# rn_mk2.net
KiCad netlist of a schematic drawn in EAGLE
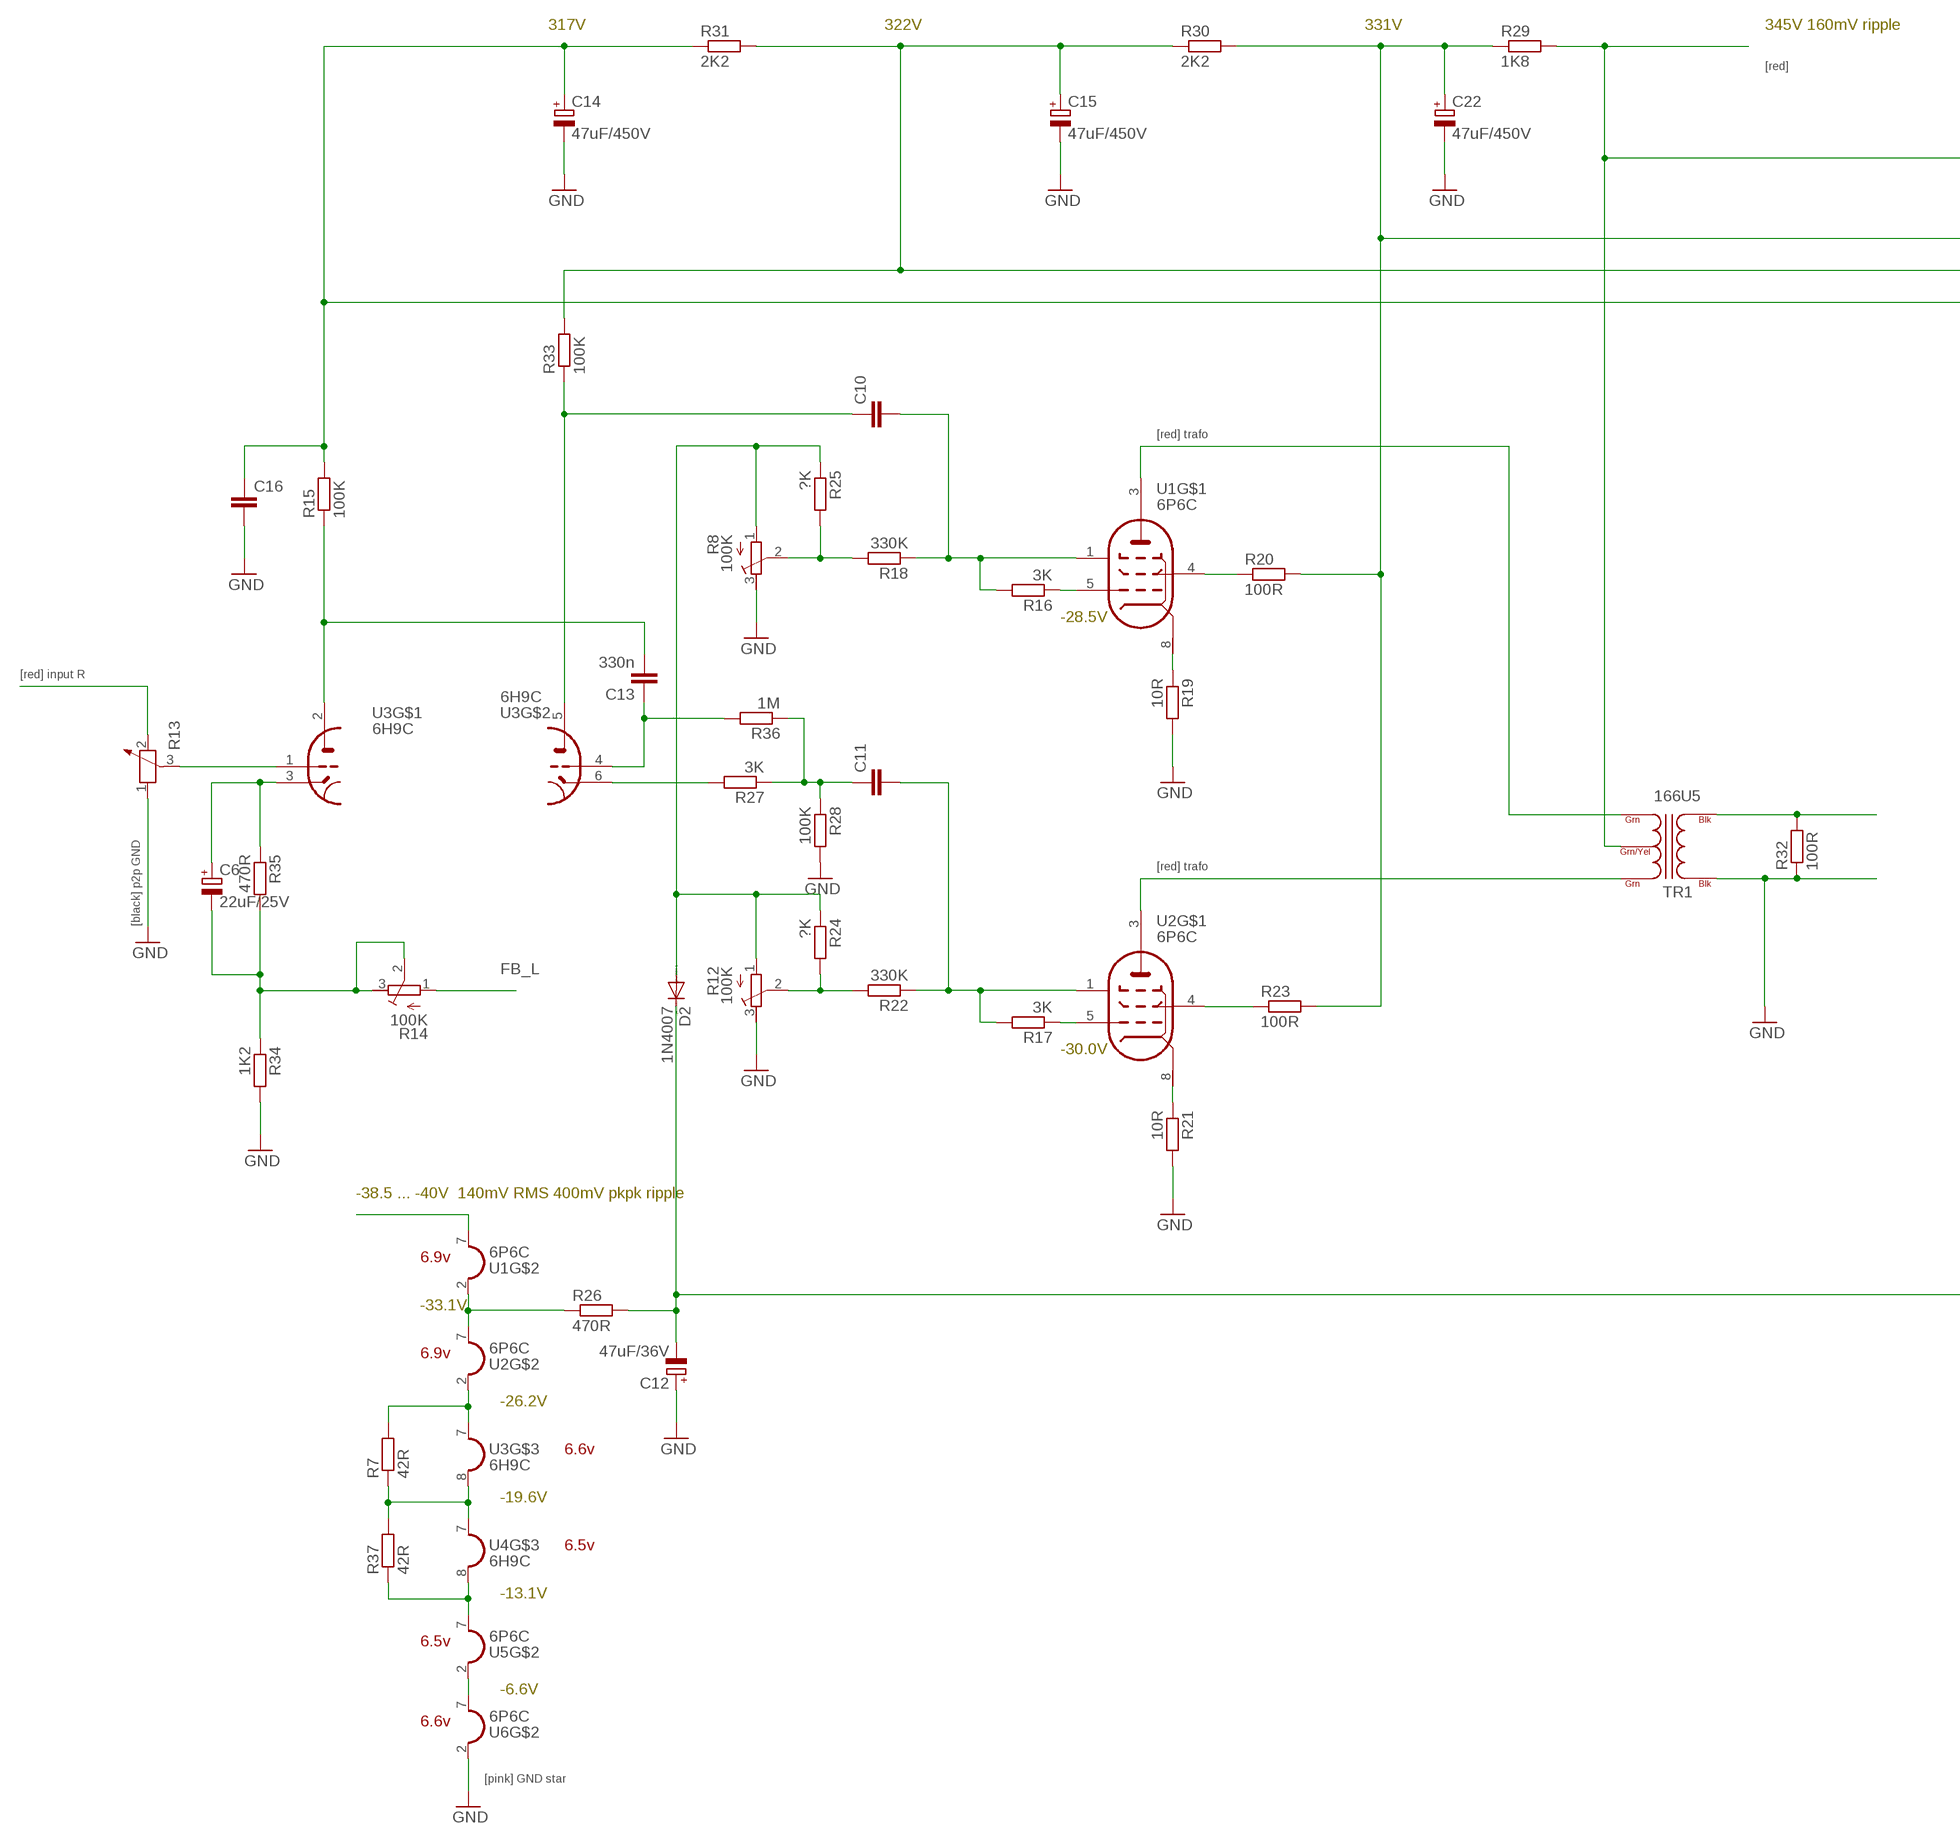
[diagram p0: schematic, sheet 1, part 1 of 2]
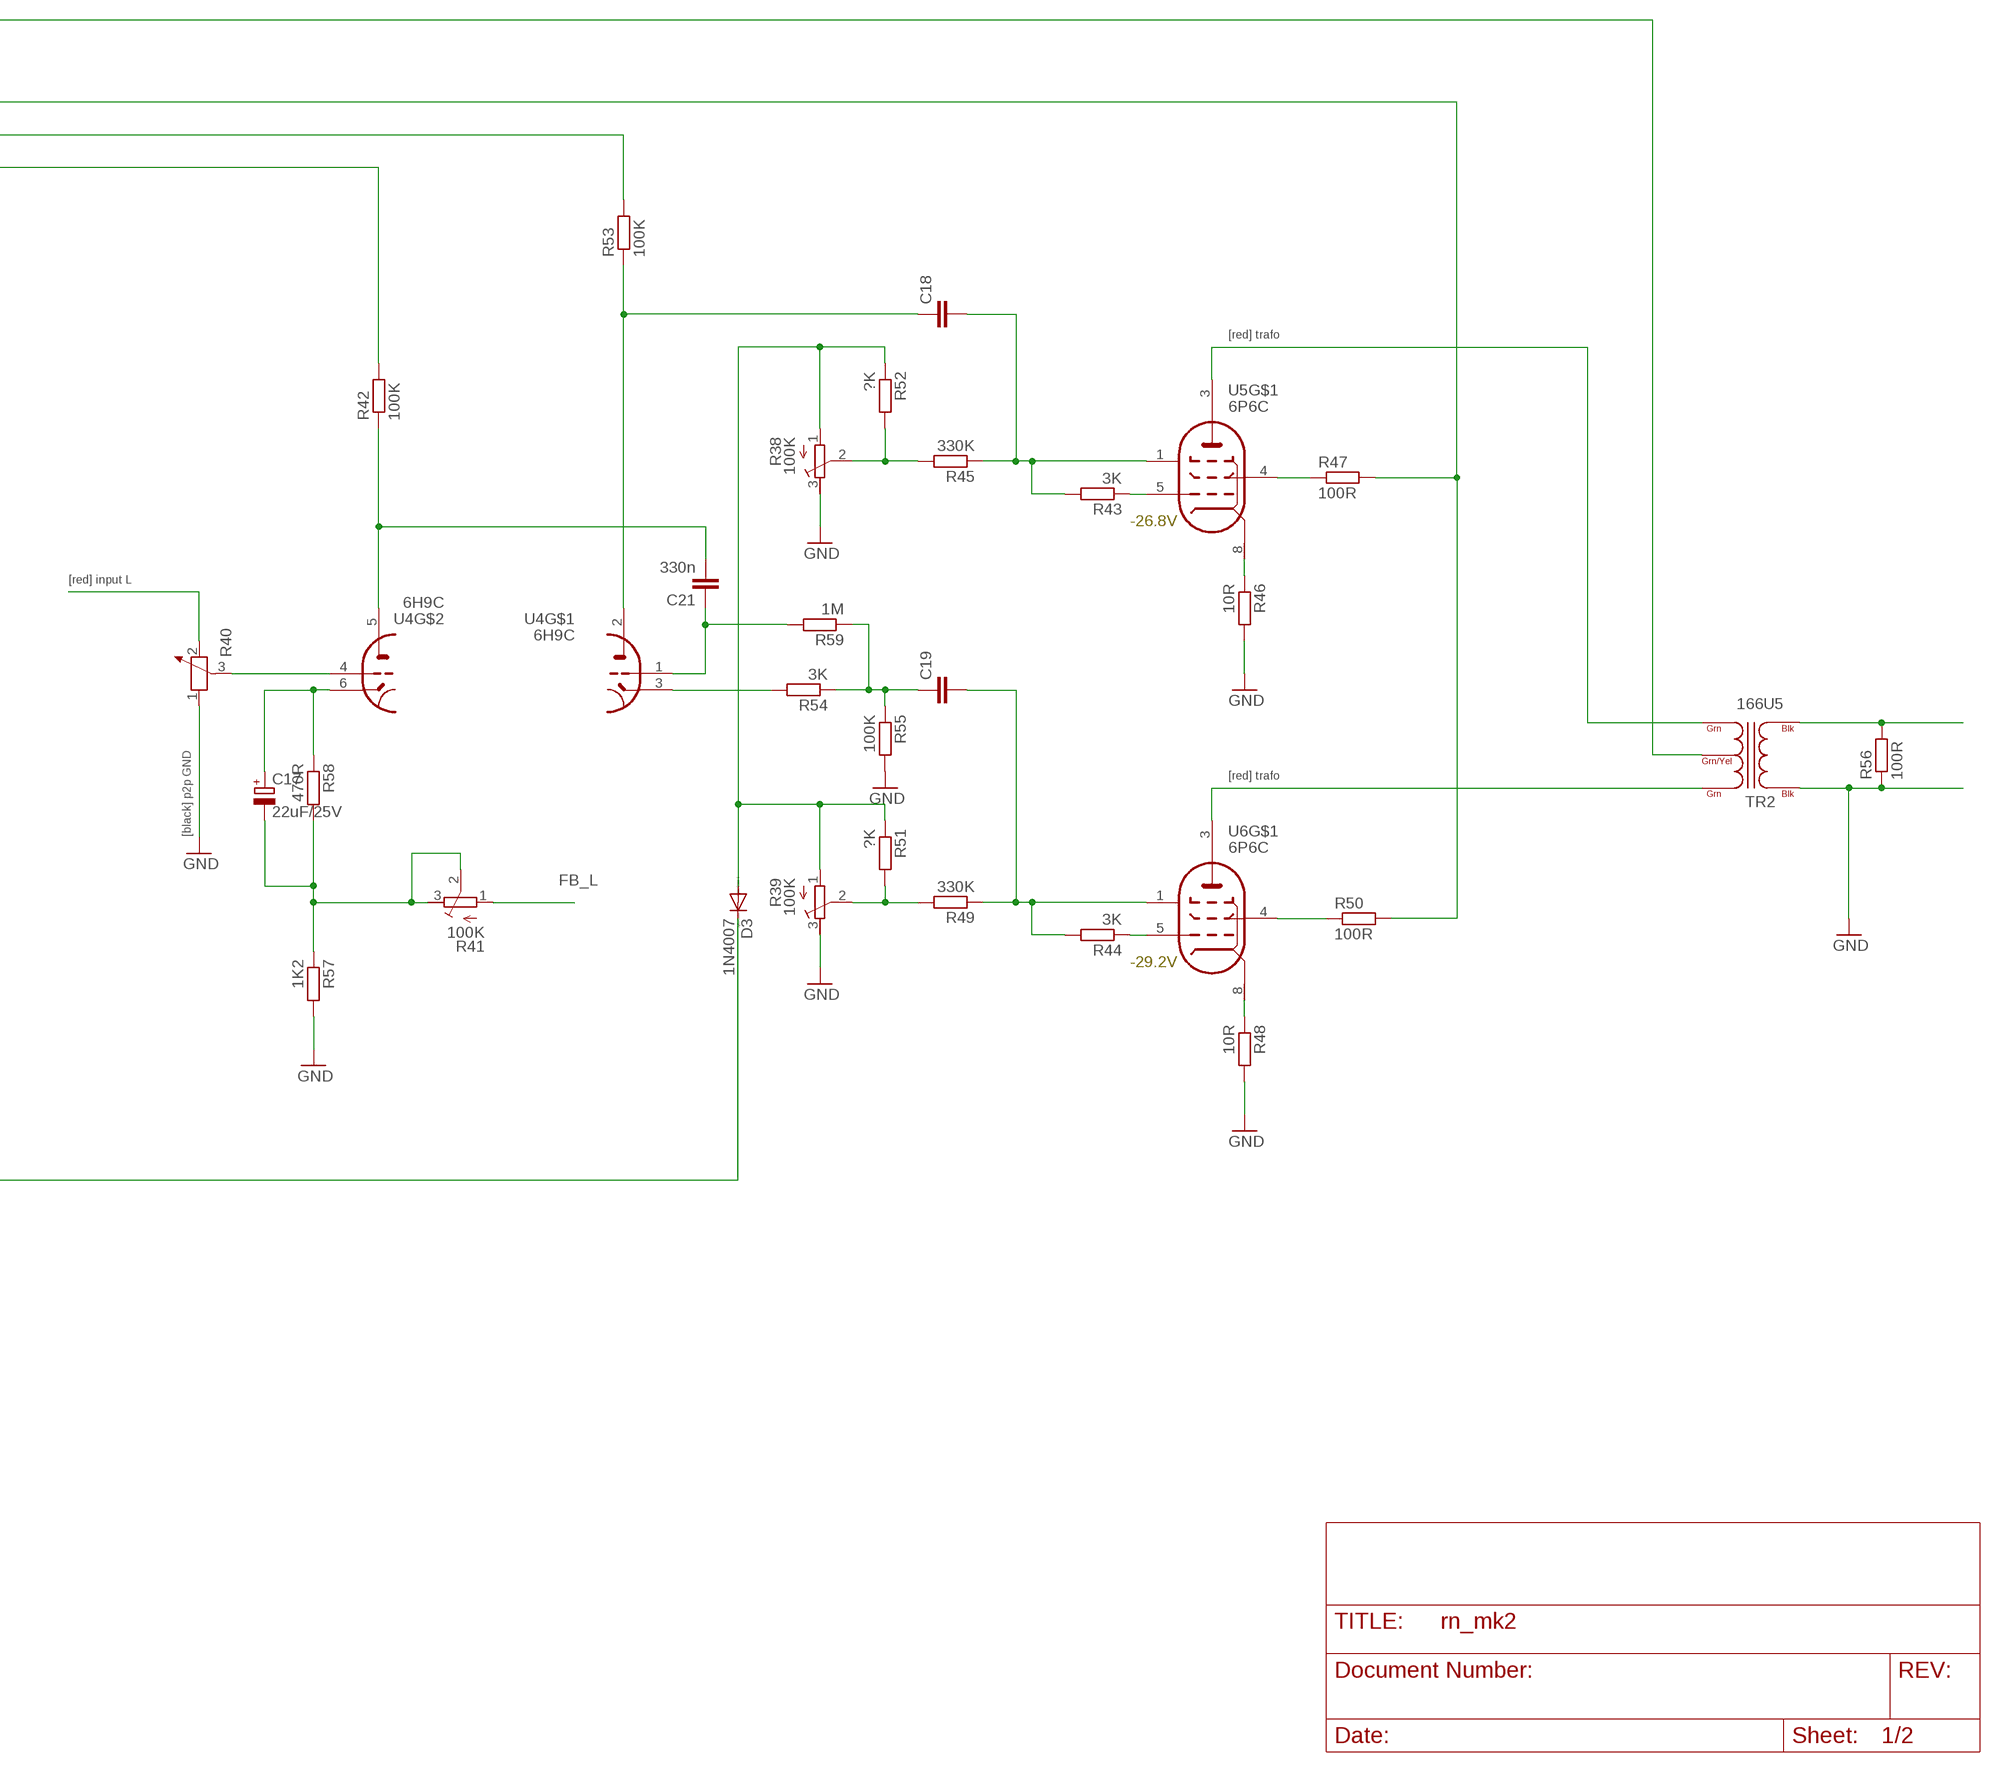
[diagram p1: schematic, sheet 1, part 2 of 2]
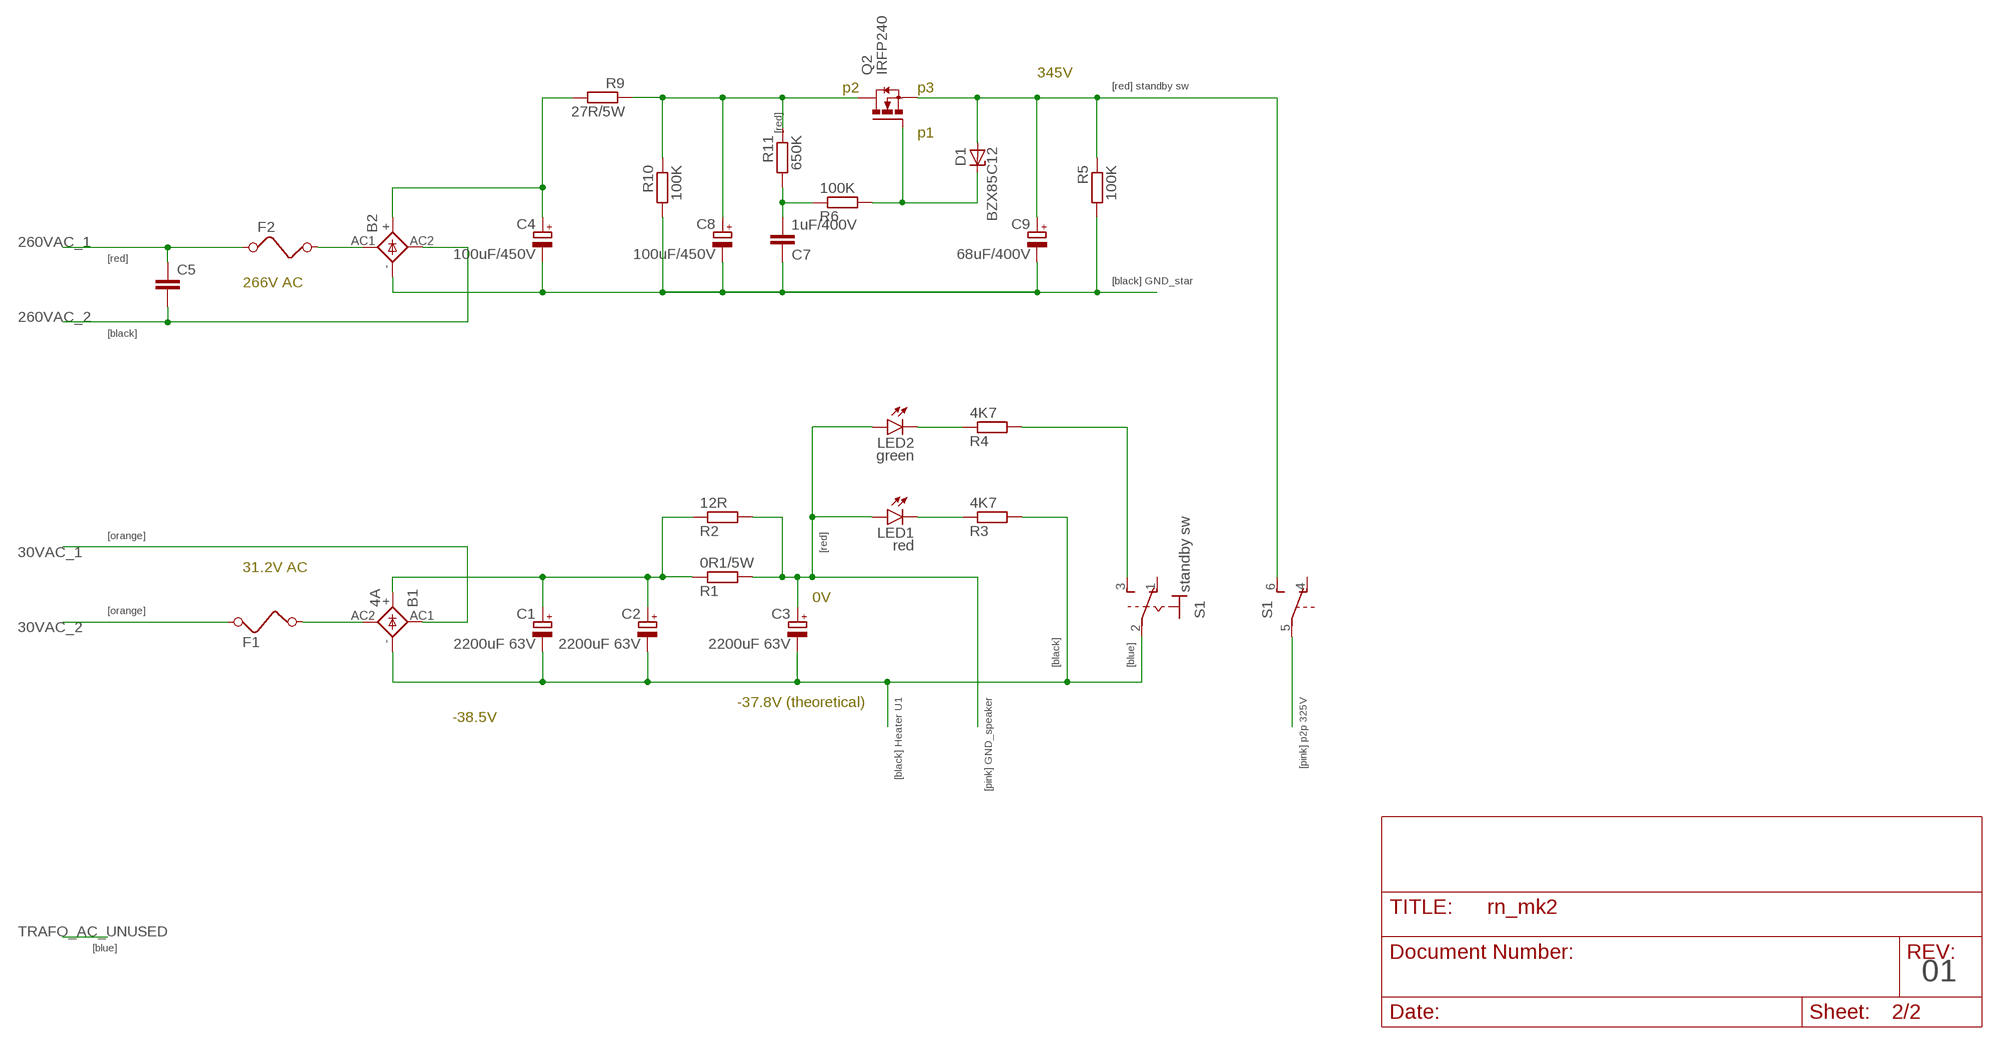
[diagram p2: schematic, sheet 2]

(export (version "E")
  (design (tool "Eeschema 10.0.6"))
  (components
    (comp (ref "B1")
      (value "4A")
      (footprint "eagle-import:DIOTEC_BC5000")
      (libsource (lib "eagle-import") (part "DIOTEC_BC5000"))
    )
    (comp (ref "B2")
      (value "DIOTEC_BC5000")
      (footprint "eagle-import:DIOTEC_BC5000")
      (libsource (lib "eagle-import") (part "DIOTEC_BC5000"))
    )
    (comp (ref "C1")
      (value "2200uF 63V")
      (footprint "eagle-import:E7,5-18")
      (libsource (lib "eagle-import") (part "CPOL-EUE7.5-18"))
    )
    (comp (ref "C2")
      (value "2200uF 63V")
      (footprint "eagle-import:E7,5-18")
      (libsource (lib "eagle-import") (part "CPOL-EUE7.5-18"))
    )
    (comp (ref "C3")
      (value "2200uF 63V")
      (footprint "eagle-import:E7,5-18")
      (libsource (lib "eagle-import") (part "CPOL-EUE7.5-18"))
    )
    (comp (ref "C4")
      (value "100uF/450V")
      (footprint "eagle-import:E7,5-18")
      (libsource (lib "eagle-import") (part "CPOL-EUE7.5-18"))
    )
    (comp (ref "C5")
      (value "C-EU075-032X103")
      (footprint "eagle-import:C075-032X103")
      (libsource (lib "eagle-import") (part "C-EU075-032X103"))
    )
    (comp (ref "C7")
      (value "1uF/400V")
      (footprint "eagle-import:C075-032X103")
      (libsource (lib "eagle-import") (part "C-EU075-032X103"))
    )
    (comp (ref "C8")
      (value "100uF/450V")
      (footprint "eagle-import:E7,5-18")
      (libsource (lib "eagle-import") (part "CPOL-EUE7.5-18"))
    )
    (comp (ref "C9")
      (value "68uF/400V")
      (footprint "eagle-import:E7,5-18")
      (libsource (lib "eagle-import") (part "CPOL-EUE7.5-18"))
    )
    (comp (ref "D1")
      (value "BZX85C12")
      (footprint "eagle-import:DO41Z10")
      (libsource (lib "eagle-import") (part "BZX85"))
    )
    (comp (ref "F1")
      (value "FUSE")
      (footprint "eagle-import:FUSE")
      (libsource (lib "eagle-import") (part "FUSE"))
    )
    (comp (ref "F2")
      (value "FUSE")
      (footprint "eagle-import:FUSE")
      (libsource (lib "eagle-import") (part "FUSE"))
    )
    (comp (ref "LED1")
      (value "red")
      (footprint "eagle-import:LED3MM")
      (libsource (lib "eagle-import") (part "LED3MM"))
    )
    (comp (ref "LED2")
      (value "green")
      (footprint "eagle-import:LED3MM")
      (libsource (lib "eagle-import") (part "LED3MM"))
    )
    (comp (ref "Q2")
      (value "IRFP240")
      (footprint "eagle-import:TO247BV")
      (libsource (lib "eagle-import") (part "IRFP240"))
    )
    (comp (ref "R1")
      (value "0R1/5W")
      (footprint "eagle-import:0922_22")
      (libsource (lib "eagle-import") (part "R-EU_0922/22"))
    )
    (comp (ref "R2")
      (value "12R")
      (footprint "eagle-import:0922_22")
      (libsource (lib "eagle-import") (part "R-EU_0922/22"))
    )
    (comp (ref "R3")
      (value "4K7")
      (footprint "eagle-import:0922_22")
      (libsource (lib "eagle-import") (part "R-EU_0922/22"))
    )
    (comp (ref "R4")
      (value "4K7")
      (footprint "eagle-import:0922_22")
      (libsource (lib "eagle-import") (part "R-EU_0922/22"))
    )
    (comp (ref "R5")
      (value "100K")
      (footprint "eagle-import:0922_22")
      (libsource (lib "eagle-import") (part "R-EU_0922/22"))
    )
    (comp (ref "R6")
      (value "100K")
      (footprint "eagle-import:0922_22")
      (libsource (lib "eagle-import") (part "R-EU_0922/22"))
    )
    (comp (ref "R9")
      (value "27R/5W")
      (footprint "eagle-import:0922_22")
      (libsource (lib "eagle-import") (part "R-EU_0922/22"))
    )
    (comp (ref "R10")
      (value "100K")
      (footprint "eagle-import:0922_22")
      (libsource (lib "eagle-import") (part "R-EU_0922/22"))
    )
    (comp (ref "R11")
      (value "650K")
      (footprint "eagle-import:0922_22")
      (libsource (lib "eagle-import") (part "R-EU_0922/22"))
    )
    (comp (ref "S1")
      (value "standby sw")
      (footprint "eagle-import:320-938")
      (libsource (lib "eagle-import") (part "320-938"))
    )
    (comp (ref "C6")
      (value "22uF/25V")
      (footprint "eagle-import:E5-5")
      (libsource (lib "eagle-import") (part "CPOL-EUE5-5"))
    )
    (comp (ref "C10")
      (value "C-EU150-054X183")
      (footprint "eagle-import:C150-054X183")
      (libsource (lib "eagle-import") (part "C-EU150-054X183"))
    )
    (comp (ref "C11")
      (value "C-EU150-054X183")
      (footprint "eagle-import:C150-054X183")
      (libsource (lib "eagle-import") (part "C-EU150-054X183"))
    )
    (comp (ref "C12")
      (value "47uF/36V")
      (footprint "eagle-import:E5-5")
      (libsource (lib "eagle-import") (part "CPOL-EUE5-5"))
    )
    (comp (ref "C13")
      (value "330n")
      (footprint "eagle-import:C150-054X183")
      (libsource (lib "eagle-import") (part "C-EU150-054X183"))
    )
    (comp (ref "C14")
      (value "47uF/450V")
      (footprint "eagle-import:E5-5")
      (libsource (lib "eagle-import") (part "CPOL-EUE5-5"))
    )
    (comp (ref "C15")
      (value "47uF/450V")
      (footprint "eagle-import:E5-5")
      (libsource (lib "eagle-import") (part "CPOL-EUE5-5"))
    )
    (comp (ref "C16")
      (value "C-EU150-054X183")
      (footprint "eagle-import:C150-054X183")
      (libsource (lib "eagle-import") (part "C-EU150-054X183"))
    )
    (comp (ref "C17")
      (value "22uF/25V")
      (footprint "eagle-import:E5-5")
      (libsource (lib "eagle-import") (part "CPOL-EUE5-5"))
    )
    (comp (ref "C18")
      (value "C-EU150-054X183")
      (footprint "eagle-import:C150-054X183")
      (libsource (lib "eagle-import") (part "C-EU150-054X183"))
    )
    (comp (ref "C19")
      (value "C-EU150-054X183")
      (footprint "eagle-import:C150-054X183")
      (libsource (lib "eagle-import") (part "C-EU150-054X183"))
    )
    (comp (ref "C21")
      (value "330n")
      (footprint "eagle-import:C150-054X183")
      (libsource (lib "eagle-import") (part "C-EU150-054X183"))
    )
    (comp (ref "C22")
      (value "47uF/450V")
      (footprint "eagle-import:E5-5")
      (libsource (lib "eagle-import") (part "CPOL-EUE5-5"))
    )
    (comp (ref "D2")
      (value "1N4007")
      (footprint "eagle-import:DO41-10")
      (libsource (lib "eagle-import") (part "1N4004"))
    )
    (comp (ref "D3")
      (value "1N4007")
      (footprint "eagle-import:DO41-10")
      (libsource (lib "eagle-import") (part "1N4004"))
    )
    (comp (ref "R7")
      (value "42R")
      (footprint "eagle-import:0414_15")
      (libsource (lib "eagle-import") (part "R-EU_0414/15"))
    )
    (comp (ref "R8")
      (value "100K")
      (footprint "eagle-import:RTRIM64Y")
      (libsource (lib "eagle-import") (part "R-TRIMM64Y"))
    )
    (comp (ref "R12")
      (value "100K")
      (footprint "eagle-import:RTRIM64Y")
      (libsource (lib "eagle-import") (part "R-TRIMM64Y"))
    )
    (comp (ref "R13")
      (value "POTENTIOMETER_PT-10")
      (footprint "eagle-import:PT-10")
      (libsource (lib "eagle-import") (part "POTENTIOMETER_PT-10"))
    )
    (comp (ref "R14")
      (value "100K")
      (footprint "eagle-import:RTRIM64Y")
      (libsource (lib "eagle-import") (part "R-TRIMM64Y"))
    )
    (comp (ref "R15")
      (value "100K")
      (footprint "eagle-import:0414_15")
      (libsource (lib "eagle-import") (part "R-EU_0414/15"))
    )
    (comp (ref "R16")
      (value "3K")
      (footprint "eagle-import:0414_15")
      (libsource (lib "eagle-import") (part "R-EU_0414/15"))
    )
    (comp (ref "R17")
      (value "3K")
      (footprint "eagle-import:0414_15")
      (libsource (lib "eagle-import") (part "R-EU_0414/15"))
    )
    (comp (ref "R18")
      (value "330K")
      (footprint "eagle-import:0414_15")
      (libsource (lib "eagle-import") (part "R-EU_0414/15"))
    )
    (comp (ref "R19")
      (value "10R")
      (footprint "eagle-import:0414_15")
      (libsource (lib "eagle-import") (part "R-EU_0414/15"))
    )
    (comp (ref "R20")
      (value "100R")
      (footprint "eagle-import:0414_15")
      (libsource (lib "eagle-import") (part "R-EU_0414/15"))
    )
    (comp (ref "R21")
      (value "10R")
      (footprint "eagle-import:0414_15")
      (libsource (lib "eagle-import") (part "R-EU_0414/15"))
    )
    (comp (ref "R22")
      (value "330K")
      (footprint "eagle-import:0414_15")
      (libsource (lib "eagle-import") (part "R-EU_0414/15"))
    )
    (comp (ref "R23")
      (value "100R")
      (footprint "eagle-import:0414_15")
      (libsource (lib "eagle-import") (part "R-EU_0414/15"))
    )
    (comp (ref "R24")
      (value "?K")
      (footprint "eagle-import:0414_15")
      (libsource (lib "eagle-import") (part "R-EU_0414/15"))
    )
    (comp (ref "R25")
      (value "?K")
      (footprint "eagle-import:0414_15")
      (libsource (lib "eagle-import") (part "R-EU_0414/15"))
    )
    (comp (ref "R26")
      (value "470R")
      (footprint "eagle-import:0922_22")
      (libsource (lib "eagle-import") (part "R-EU_0922/22"))
    )
    (comp (ref "R27")
      (value "3K")
      (footprint "eagle-import:0414_15")
      (libsource (lib "eagle-import") (part "R-EU_0414/15"))
    )
    (comp (ref "R28")
      (value "100K")
      (footprint "eagle-import:0414_15")
      (libsource (lib "eagle-import") (part "R-EU_0414/15"))
    )
    (comp (ref "R29")
      (value "1K8")
      (footprint "eagle-import:0414_15")
      (libsource (lib "eagle-import") (part "R-EU_0414/15"))
    )
    (comp (ref "R30")
      (value "2K2")
      (footprint "eagle-import:0414_15")
      (libsource (lib "eagle-import") (part "R-EU_0414/15"))
    )
    (comp (ref "R31")
      (value "2K2")
      (footprint "eagle-import:0414_15")
      (libsource (lib "eagle-import") (part "R-EU_0414/15"))
    )
    (comp (ref "R32")
      (value "100R")
      (footprint "eagle-import:0414_15")
      (libsource (lib "eagle-import") (part "R-EU_0414/15"))
    )
    (comp (ref "R33")
      (value "100K")
      (footprint "eagle-import:0414_15")
      (libsource (lib "eagle-import") (part "R-EU_0414/15"))
    )
    (comp (ref "R34")
      (value "1K2")
      (footprint "eagle-import:0414_15")
      (libsource (lib "eagle-import") (part "R-EU_0414/15"))
    )
    (comp (ref "R35")
      (value "470R")
      (footprint "eagle-import:0414_15")
      (libsource (lib "eagle-import") (part "R-EU_0414/15"))
    )
    (comp (ref "R36")
      (value "1M")
      (footprint "eagle-import:0414_15")
      (libsource (lib "eagle-import") (part "R-EU_0414/15"))
    )
    (comp (ref "R37")
      (value "42R")
      (footprint "eagle-import:0414_15")
      (libsource (lib "eagle-import") (part "R-EU_0414/15"))
    )
    (comp (ref "R38")
      (value "100K")
      (footprint "eagle-import:RTRIM64Y")
      (libsource (lib "eagle-import") (part "R-TRIMM64Y"))
    )
    (comp (ref "R39")
      (value "100K")
      (footprint "eagle-import:RTRIM64Y")
      (libsource (lib "eagle-import") (part "R-TRIMM64Y"))
    )
    (comp (ref "R40")
      (value "POTENTIOMETER_PT-10")
      (footprint "eagle-import:PT-10")
      (libsource (lib "eagle-import") (part "POTENTIOMETER_PT-10"))
    )
    (comp (ref "R41")
      (value "100K")
      (footprint "eagle-import:RTRIM64Y")
      (libsource (lib "eagle-import") (part "R-TRIMM64Y"))
    )
    (comp (ref "R42")
      (value "100K")
      (footprint "eagle-import:0414_15")
      (libsource (lib "eagle-import") (part "R-EU_0414/15"))
    )
    (comp (ref "R43")
      (value "3K")
      (footprint "eagle-import:0414_15")
      (libsource (lib "eagle-import") (part "R-EU_0414/15"))
    )
    (comp (ref "R44")
      (value "3K")
      (footprint "eagle-import:0414_15")
      (libsource (lib "eagle-import") (part "R-EU_0414/15"))
    )
    (comp (ref "R45")
      (value "330K")
      (footprint "eagle-import:0414_15")
      (libsource (lib "eagle-import") (part "R-EU_0414/15"))
    )
    (comp (ref "R46")
      (value "10R")
      (footprint "eagle-import:0414_15")
      (libsource (lib "eagle-import") (part "R-EU_0414/15"))
    )
    (comp (ref "R47")
      (value "100R")
      (footprint "eagle-import:0414_15")
      (libsource (lib "eagle-import") (part "R-EU_0414/15"))
    )
    (comp (ref "R48")
      (value "10R")
      (footprint "eagle-import:0414_15")
      (libsource (lib "eagle-import") (part "R-EU_0414/15"))
    )
    (comp (ref "R49")
      (value "330K")
      (footprint "eagle-import:0414_15")
      (libsource (lib "eagle-import") (part "R-EU_0414/15"))
    )
    (comp (ref "R50")
      (value "100R")
      (footprint "eagle-import:0414_15")
      (libsource (lib "eagle-import") (part "R-EU_0414/15"))
    )
    (comp (ref "R51")
      (value "?K")
      (footprint "eagle-import:0414_15")
      (libsource (lib "eagle-import") (part "R-EU_0414/15"))
    )
    (comp (ref "R52")
      (value "?K")
      (footprint "eagle-import:0414_15")
      (libsource (lib "eagle-import") (part "R-EU_0414/15"))
    )
    (comp (ref "R53")
      (value "100K")
      (footprint "eagle-import:0414_15")
      (libsource (lib "eagle-import") (part "R-EU_0414/15"))
    )
    (comp (ref "R54")
      (value "3K")
      (footprint "eagle-import:0414_15")
      (libsource (lib "eagle-import") (part "R-EU_0414/15"))
    )
    (comp (ref "R55")
      (value "100K")
      (footprint "eagle-import:0414_15")
      (libsource (lib "eagle-import") (part "R-EU_0414/15"))
    )
    (comp (ref "R56")
      (value "100R")
      (footprint "eagle-import:0414_15")
      (libsource (lib "eagle-import") (part "R-EU_0414/15"))
    )
    (comp (ref "R57")
      (value "1K2")
      (footprint "eagle-import:0414_15")
      (libsource (lib "eagle-import") (part "R-EU_0414/15"))
    )
    (comp (ref "R58")
      (value "470R")
      (footprint "eagle-import:0414_15")
      (libsource (lib "eagle-import") (part "R-EU_0414/15"))
    )
    (comp (ref "R59")
      (value "1M")
      (footprint "eagle-import:0414_15")
      (libsource (lib "eagle-import") (part "R-EU_0414/15"))
    )
    (comp (ref "TR1")
      (value "166U5")
      (footprint "eagle-import:C14H")
      (libsource (lib "eagle-import") (part "166U5"))
    )
    (comp (ref "TR2")
      (value "166U5")
      (footprint "eagle-import:C14H")
      (libsource (lib "eagle-import") (part "166U5"))
    )
    (comp (ref "U1")
      (value "6P6C")
      (footprint "eagle-import:OKTAL")
      (libsource (lib "eagle-import") (part "6P6C"))
    )
    (comp (ref "U2")
      (value "6P6C")
      (footprint "eagle-import:OKTAL")
      (libsource (lib "eagle-import") (part "6P6C"))
    )
    (comp (ref "U3")
      (value "6H9C")
      (footprint "eagle-import:OKTAL")
      (libsource (lib "eagle-import") (part "6H9C"))
    )
    (comp (ref "U4")
      (value "6H9C")
      (footprint "eagle-import:OKTAL")
      (libsource (lib "eagle-import") (part "6H9C"))
    )
    (comp (ref "U5")
      (value "6P6C")
      (footprint "eagle-import:OKTAL")
      (libsource (lib "eagle-import") (part "6P6C"))
    )
    (comp (ref "U6")
      (value "6P6C")
      (footprint "eagle-import:OKTAL")
      (libsource (lib "eagle-import") (part "6P6C"))
    )
  )
  (nets
    (net (code "1") (name "30VAC_1") (class "Default")
      (node (ref "B1") (pin "AC1") (pinfunction "AC1_AC1") (pintype "passive"))
    )
    (net (code "2") (name "30VAC_2") (class "Default")
      (node (ref "F1") (pin "1") (pinfunction "1_1") (pintype "passive"))
    )
    (net (code "3") (name "260VAC_1") (class "Default")
      (node (ref "C5") (pin "1") (pinfunction "1_1") (pintype "passive"))
      (node (ref "F2") (pin "1") (pinfunction "1_1") (pintype "passive"))
    )
    (net (code "4") (name "260VAC_2") (class "Default")
      (node (ref "B2") (pin "AC2") (pinfunction "AC2_AC2") (pintype "passive"))
      (node (ref "C5") (pin "2") (pinfunction "2_2") (pintype "passive"))
    )
    (net (code "5") (name "FB_L") (class "Default")
      (node (ref "R14") (pin "1") (pinfunction "A_1") (pintype "passive"))
      (node (ref "R41") (pin "1") (pinfunction "A_1") (pintype "passive"))
    )
    (net (code "6") (name "GND") (class "Default")
      (node (ref "C12") (pin "+") (pinfunction "+_+") (pintype "passive"))
      (node (ref "C14") (pin "-") (pinfunction "-_-") (pintype "passive"))
      (node (ref "C15") (pin "-") (pinfunction "-_-") (pintype "passive"))
      (node (ref "C16") (pin "2") (pinfunction "2_2") (pintype "passive"))
      (node (ref "C22") (pin "-") (pinfunction "-_-") (pintype "passive"))
      (node (ref "R12") (pin "3") (pinfunction "E_3") (pintype "passive"))
      (node (ref "R13") (pin "1") (pinfunction "1_1") (pintype "passive"))
      (node (ref "R19") (pin "2") (pinfunction "2_2") (pintype "passive"))
      (node (ref "R21") (pin "2") (pinfunction "2_2") (pintype "passive"))
      (node (ref "R28") (pin "2") (pinfunction "2_2") (pintype "passive"))
      (node (ref "R32") (pin "1") (pinfunction "1_1") (pintype "passive"))
      (node (ref "R34") (pin "2") (pinfunction "2_2") (pintype "passive"))
      (node (ref "R38") (pin "3") (pinfunction "E_3") (pintype "passive"))
      (node (ref "R39") (pin "3") (pinfunction "E_3") (pintype "passive"))
      (node (ref "R40") (pin "1") (pinfunction "1_1") (pintype "passive"))
      (node (ref "R46") (pin "2") (pinfunction "2_2") (pintype "passive"))
      (node (ref "R48") (pin "2") (pinfunction "2_2") (pintype "passive"))
      (node (ref "R55") (pin "2") (pinfunction "2_2") (pintype "passive"))
      (node (ref "R56") (pin "1") (pinfunction "1_1") (pintype "passive"))
      (node (ref "R57") (pin "2") (pinfunction "2_2") (pintype "passive"))
      (node (ref "R8") (pin "3") (pinfunction "E_3") (pintype "passive"))
      (node (ref "TR1") (pin "BLK@1") (pinfunction "BLK_BLK@1") (pintype "passive"))
      (node (ref "TR2") (pin "BLK@1") (pinfunction "BLK_BLK@1") (pintype "passive"))
      (node (ref "U6") (pin "2") (pinfunction "H1_2") (pintype "passive"))
    )
    (net (code "7") (name "Net-(B1-Pad+)") (class "Default")
      (node (ref "B1") (pin "+") (pinfunction "+_+") (pintype "passive"))
      (node (ref "C1") (pin "+") (pinfunction "+_+") (pintype "passive"))
      (node (ref "C2") (pin "+") (pinfunction "+_+") (pintype "passive"))
      (node (ref "R1") (pin "1") (pinfunction "1_1") (pintype "passive"))
      (node (ref "R2") (pin "1") (pinfunction "1_1") (pintype "passive"))
    )
    (net (code "8") (name "Net-(B1-PadAC2)") (class "Default")
      (node (ref "B1") (pin "AC2") (pinfunction "AC2_AC2") (pintype "passive"))
      (node (ref "F1") (pin "2") (pinfunction "2_2") (pintype "passive"))
    )
    (net (code "9") (name "Net-(B2-Pad+)") (class "Default")
      (node (ref "B2") (pin "+") (pinfunction "+_+") (pintype "passive"))
      (node (ref "C4") (pin "+") (pinfunction "+_+") (pintype "passive"))
      (node (ref "R9") (pin "2") (pinfunction "2_2") (pintype "passive"))
    )
    (net (code "10") (name "Net-(B2-Pad-)") (class "Default")
      (node (ref "B2") (pin "-") (pinfunction "-_-") (pintype "passive"))
      (node (ref "C4") (pin "-") (pinfunction "-_-") (pintype "passive"))
      (node (ref "C7") (pin "1") (pinfunction "1_1") (pintype "passive"))
      (node (ref "C8") (pin "-") (pinfunction "-_-") (pintype "passive"))
      (node (ref "C9") (pin "-") (pinfunction "-_-") (pintype "passive"))
      (node (ref "R10") (pin "2") (pinfunction "2_2") (pintype "passive"))
      (node (ref "R5") (pin "2") (pinfunction "2_2") (pintype "passive"))
    )
    (net (code "11") (name "Net-(B2-PadAC1)") (class "Default")
      (node (ref "B2") (pin "AC1") (pinfunction "AC1_AC1") (pintype "passive"))
      (node (ref "F2") (pin "2") (pinfunction "2_2") (pintype "passive"))
    )
    (net (code "12") (name "Net-(C3-Pad+)") (class "Default")
      (node (ref "C3") (pin "+") (pinfunction "+_+") (pintype "passive"))
      (node (ref "LED1") (pin "A") (pinfunction "A_A") (pintype "passive"))
      (node (ref "LED2") (pin "A") (pinfunction "A_A") (pintype "passive"))
      (node (ref "R1") (pin "2") (pinfunction "2_2") (pintype "passive"))
      (node (ref "R2") (pin "2") (pinfunction "2_2") (pintype "passive"))
    )
    (net (code "13") (name "Net-(C7-Pad2)") (class "Default")
      (node (ref "C7") (pin "2") (pinfunction "2_2") (pintype "passive"))
      (node (ref "R11") (pin "2") (pinfunction "2_2") (pintype "passive"))
      (node (ref "R6") (pin "1") (pinfunction "1_1") (pintype "passive"))
    )
    (net (code "14") (name "Net-(C8-Pad+)") (class "Default")
      (node (ref "C8") (pin "+") (pinfunction "+_+") (pintype "passive"))
      (node (ref "Q2") (pin "D") (pinfunction "D_D") (pintype "passive"))
      (node (ref "R10") (pin "1") (pinfunction "1_1") (pintype "passive"))
      (node (ref "R11") (pin "1") (pinfunction "1_1") (pintype "passive"))
      (node (ref "R9") (pin "1") (pinfunction "1_1") (pintype "passive"))
    )
    (net (code "15") (name "Net-(C11-Pad1)") (class "Default")
      (node (ref "C11") (pin "1") (pinfunction "1_1") (pintype "passive"))
      (node (ref "R27") (pin "1") (pinfunction "1_1") (pintype "passive"))
      (node (ref "R28") (pin "1") (pinfunction "1_1") (pintype "passive"))
      (node (ref "R36") (pin "1") (pinfunction "1_1") (pintype "passive"))
    )
    (net (code "16") (name "Net-(C12-Pad-)") (class "Default")
      (node (ref "C12") (pin "-") (pinfunction "-_-") (pintype "passive"))
      (node (ref "D2") (pin "C") (pinfunction "C_C") (pintype "passive"))
      (node (ref "D3") (pin "C") (pinfunction "C_C") (pintype "passive"))
      (node (ref "R26") (pin "2") (pinfunction "2_2") (pintype "passive"))
    )
    (net (code "17") (name "Net-(C14-Pad+)") (class "Default")
      (node (ref "C14") (pin "+") (pinfunction "+_+") (pintype "passive"))
      (node (ref "C16") (pin "1") (pinfunction "1_1") (pintype "passive"))
      (node (ref "R15") (pin "2") (pinfunction "2_2") (pintype "passive"))
      (node (ref "R31") (pin "1") (pinfunction "1_1") (pintype "passive"))
      (node (ref "R42") (pin "2") (pinfunction "2_2") (pintype "passive"))
    )
    (net (code "18") (name "Net-(C15-Pad+)") (class "Default")
      (node (ref "C15") (pin "+") (pinfunction "+_+") (pintype "passive"))
      (node (ref "R30") (pin "1") (pinfunction "1_1") (pintype "passive"))
      (node (ref "R31") (pin "2") (pinfunction "2_2") (pintype "passive"))
      (node (ref "R33") (pin "2") (pinfunction "2_2") (pintype "passive"))
      (node (ref "R53") (pin "2") (pinfunction "2_2") (pintype "passive"))
    )
    (net (code "19") (name "Net-(C19-Pad1)") (class "Default")
      (node (ref "C19") (pin "1") (pinfunction "1_1") (pintype "passive"))
      (node (ref "R54") (pin "1") (pinfunction "1_1") (pintype "passive"))
      (node (ref "R55") (pin "1") (pinfunction "1_1") (pintype "passive"))
      (node (ref "R59") (pin "1") (pinfunction "1_1") (pintype "passive"))
    )
    (net (code "20") (name "Net-(C22-Pad+)") (class "Default")
      (node (ref "C22") (pin "+") (pinfunction "+_+") (pintype "passive"))
      (node (ref "R20") (pin "2") (pinfunction "2_2") (pintype "passive"))
      (node (ref "R23") (pin "2") (pinfunction "2_2") (pintype "passive"))
      (node (ref "R29") (pin "1") (pinfunction "1_1") (pintype "passive"))
      (node (ref "R30") (pin "2") (pinfunction "2_2") (pintype "passive"))
      (node (ref "R47") (pin "2") (pinfunction "2_2") (pintype "passive"))
      (node (ref "R50") (pin "2") (pinfunction "2_2") (pintype "passive"))
    )
    (net (code "21") (name "Net-(D1-PadC)") (class "Default")
      (node (ref "D1") (pin "C") (pinfunction "C_C") (pintype "passive"))
      (node (ref "Q2") (pin "G") (pinfunction "G_G") (pintype "passive"))
      (node (ref "R6") (pin "2") (pinfunction "2_2") (pintype "passive"))
    )
    (net (code "22") (name "Net-(LED1-C)") (class "Default")
      (node (ref "LED1") (pin "K") (pinfunction "C_K") (pintype "passive"))
      (node (ref "R3") (pin "1") (pinfunction "1_1") (pintype "passive"))
    )
    (net (code "23") (name "Net-(LED2-C)") (class "Default")
      (node (ref "LED2") (pin "K") (pinfunction "C_K") (pintype "passive"))
      (node (ref "R4") (pin "1") (pinfunction "1_1") (pintype "passive"))
    )
    (net (code "24") (name "Net-(R8-S)") (class "Default")
      (node (ref "R18") (pin "2") (pinfunction "2_2") (pintype "passive"))
      (node (ref "R25") (pin "2") (pinfunction "2_2") (pintype "passive"))
      (node (ref "R8") (pin "2") (pinfunction "S_2") (pintype "passive"))
    )
    (net (code "25") (name "Net-(R12-A)") (class "Default")
      (node (ref "D2") (pin "A") (pinfunction "A_A") (pintype "passive"))
      (node (ref "R12") (pin "1") (pinfunction "A_1") (pintype "passive"))
      (node (ref "R24") (pin "1") (pinfunction "1_1") (pintype "passive"))
      (node (ref "R25") (pin "1") (pinfunction "1_1") (pintype "passive"))
      (node (ref "R8") (pin "1") (pinfunction "A_1") (pintype "passive"))
    )
    (net (code "26") (name "Net-(R12-S)") (class "Default")
      (node (ref "R12") (pin "2") (pinfunction "S_2") (pintype "passive"))
      (node (ref "R22") (pin "2") (pinfunction "2_2") (pintype "passive"))
      (node (ref "R24") (pin "2") (pinfunction "2_2") (pintype "passive"))
    )
    (net (code "27") (name "Net-(R14-E)") (class "Default")
      (node (ref "C6") (pin "-") (pinfunction "-_-") (pintype "passive"))
      (node (ref "R14") (pin "2") (pinfunction "S_2") (pintype "passive"))
      (node (ref "R14") (pin "3") (pinfunction "E_3") (pintype "passive"))
      (node (ref "R34") (pin "1") (pinfunction "1_1") (pintype "passive"))
      (node (ref "R35") (pin "2") (pinfunction "2_2") (pintype "passive"))
    )
    (net (code "28") (name "Net-(R29-Pad2)") (class "Default")
      (node (ref "R29") (pin "2") (pinfunction "2_2") (pintype "passive"))
      (node (ref "TR1") (pin "GRN/YEL") (pinfunction "GRN/YEL_GRN/YEL") (pintype "passive"))
      (node (ref "TR2") (pin "GRN/YEL") (pinfunction "GRN/YEL_GRN/YEL") (pintype "passive"))
    )
    (net (code "29") (name "Net-(R32-Pad2)") (class "Default")
      (node (ref "R32") (pin "2") (pinfunction "2_2") (pintype "passive"))
      (node (ref "TR1") (pin "BLK@2") (pinfunction "BLK_BLK@2") (pintype "passive"))
    )
    (net (code "30") (name "Net-(R38-A)") (class "Default")
      (node (ref "D3") (pin "A") (pinfunction "A_A") (pintype "passive"))
      (node (ref "R38") (pin "1") (pinfunction "A_1") (pintype "passive"))
      (node (ref "R39") (pin "1") (pinfunction "A_1") (pintype "passive"))
      (node (ref "R51") (pin "1") (pinfunction "1_1") (pintype "passive"))
      (node (ref "R52") (pin "1") (pinfunction "1_1") (pintype "passive"))
    )
    (net (code "31") (name "Net-(R38-S)") (class "Default")
      (node (ref "R38") (pin "2") (pinfunction "S_2") (pintype "passive"))
      (node (ref "R45") (pin "2") (pinfunction "2_2") (pintype "passive"))
      (node (ref "R52") (pin "2") (pinfunction "2_2") (pintype "passive"))
    )
    (net (code "32") (name "Net-(R39-S)") (class "Default")
      (node (ref "R39") (pin "2") (pinfunction "S_2") (pintype "passive"))
      (node (ref "R49") (pin "2") (pinfunction "2_2") (pintype "passive"))
      (node (ref "R51") (pin "2") (pinfunction "2_2") (pintype "passive"))
    )
    (net (code "33") (name "Net-(R41-E)") (class "Default")
      (node (ref "C17") (pin "-") (pinfunction "-_-") (pintype "passive"))
      (node (ref "R41") (pin "2") (pinfunction "S_2") (pintype "passive"))
      (node (ref "R41") (pin "3") (pinfunction "E_3") (pintype "passive"))
      (node (ref "R57") (pin "1") (pinfunction "1_1") (pintype "passive"))
      (node (ref "R58") (pin "2") (pinfunction "2_2") (pintype "passive"))
    )
    (net (code "34") (name "Net-(R56-Pad2)") (class "Default")
      (node (ref "R56") (pin "2") (pinfunction "2_2") (pintype "passive"))
      (node (ref "TR2") (pin "BLK@2") (pinfunction "BLK_BLK@2") (pintype "passive"))
    )
    (net (code "35") (name "Net-(S1A-P)") (class "Default")
      (node (ref "B1") (pin "-") (pinfunction "-_-") (pintype "passive"))
      (node (ref "C1") (pin "-") (pinfunction "-_-") (pintype "passive"))
      (node (ref "C2") (pin "-") (pinfunction "-_-") (pintype "passive"))
      (node (ref "C3") (pin "-") (pinfunction "-_-") (pintype "passive"))
      (node (ref "R3") (pin "2") (pinfunction "2_2") (pintype "passive"))
      (node (ref "S1") (pin "2") (pinfunction "P_2") (pintype "passive"))
    )
    (net (code "36") (name "Net-(S1A-S)") (class "Default")
      (node (ref "R4") (pin "2") (pinfunction "2_2") (pintype "passive"))
      (node (ref "S1") (pin "3") (pinfunction "S_3") (pintype "passive"))
    )
    (net (code "37") (name "Net-(S1B-S)") (class "Default")
      (node (ref "C9") (pin "+") (pinfunction "+_+") (pintype "passive"))
      (node (ref "D1") (pin "A") (pinfunction "A_A") (pintype "passive"))
      (node (ref "Q2") (pin "S") (pinfunction "S_S") (pintype "passive"))
      (node (ref "R5") (pin "1") (pinfunction "1_1") (pintype "passive"))
      (node (ref "S1") (pin "6") (pinfunction "S_6") (pintype "passive"))
    )
    (net (code "38") (name "Net-(U1A-PA)") (class "Default")
      (node (ref "TR1") (pin "GRN@2") (pinfunction "GRN_GRN@2") (pintype "passive"))
      (node (ref "U1") (pin "3") (pinfunction "PA_3") (pintype "passive"))
    )
    (net (code "39") (name "Net-(U1A-PG)") (class "Default")
      (node (ref "R16") (pin "1") (pinfunction "1_1") (pintype "passive"))
      (node (ref "U1") (pin "5") (pinfunction "PG_5") (pintype "passive"))
    )
    (net (code "40") (name "Net-(U1A-PK)") (class "Default")
      (node (ref "R19") (pin "1") (pinfunction "1_1") (pintype "passive"))
      (node (ref "U1") (pin "8") (pinfunction "PK_8") (pintype "passive"))
    )
    (net (code "41") (name "Net-(U1A-PSG)") (class "Default")
      (node (ref "R20") (pin "1") (pinfunction "1_1") (pintype "passive"))
      (node (ref "U1") (pin "4") (pinfunction "PSG_4") (pintype "passive"))
    )
    (net (code "42") (name "Net-(U1A-SH)") (class "Default")
      (node (ref "C10") (pin "2") (pinfunction "2_2") (pintype "passive"))
      (node (ref "R16") (pin "2") (pinfunction "2_2") (pintype "passive"))
      (node (ref "R18") (pin "1") (pinfunction "1_1") (pintype "passive"))
      (node (ref "U1") (pin "1") (pinfunction "SH_1") (pintype "passive"))
    )
    (net (code "43") (name "Net-(U1B-H1)") (class "Default")
      (node (ref "R26") (pin "1") (pinfunction "1_1") (pintype "passive"))
      (node (ref "U1") (pin "2") (pinfunction "H1_2") (pintype "passive"))
      (node (ref "U2") (pin "7") (pinfunction "H2_7") (pintype "passive"))
    )
    (net (code "44") (name "Net-(U2A-PA)") (class "Default")
      (node (ref "TR1") (pin "GRN@1") (pinfunction "GRN_GRN@1") (pintype "passive"))
      (node (ref "U2") (pin "3") (pinfunction "PA_3") (pintype "passive"))
    )
    (net (code "45") (name "Net-(U2A-PG)") (class "Default")
      (node (ref "R17") (pin "1") (pinfunction "1_1") (pintype "passive"))
      (node (ref "U2") (pin "5") (pinfunction "PG_5") (pintype "passive"))
    )
    (net (code "46") (name "Net-(U2A-PK)") (class "Default")
      (node (ref "R21") (pin "1") (pinfunction "1_1") (pintype "passive"))
      (node (ref "U2") (pin "8") (pinfunction "PK_8") (pintype "passive"))
    )
    (net (code "47") (name "Net-(U2A-PSG)") (class "Default")
      (node (ref "R23") (pin "1") (pinfunction "1_1") (pintype "passive"))
      (node (ref "U2") (pin "4") (pinfunction "PSG_4") (pintype "passive"))
    )
    (net (code "48") (name "Net-(U2A-SH)") (class "Default")
      (node (ref "C11") (pin "2") (pinfunction "2_2") (pintype "passive"))
      (node (ref "R17") (pin "2") (pinfunction "2_2") (pintype "passive"))
      (node (ref "R22") (pin "1") (pinfunction "1_1") (pintype "passive"))
      (node (ref "U2") (pin "1") (pinfunction "SH_1") (pintype "passive"))
    )
    (net (code "49") (name "Net-(U2B-H1)") (class "Default")
      (node (ref "R7") (pin "2") (pinfunction "2_2") (pintype "passive"))
      (node (ref "U2") (pin "2") (pinfunction "H1_2") (pintype "passive"))
      (node (ref "U3") (pin "7") (pinfunction "H1_7") (pintype "passive"))
    )
    (net (code "50") (name "Net-(U3A-T1)") (class "Default")
      (node (ref "C6") (pin "+") (pinfunction "+_+") (pintype "passive"))
      (node (ref "R35") (pin "1") (pinfunction "1_1") (pintype "passive"))
      (node (ref "U3") (pin "3") (pinfunction "T1_3") (pintype "passive"))
    )
    (net (code "51") (name "Net-(U3A-TA1)") (class "Default")
      (node (ref "C13") (pin "2") (pinfunction "2_2") (pintype "passive"))
      (node (ref "R15") (pin "1") (pinfunction "1_1") (pintype "passive"))
      (node (ref "U3") (pin "2") (pinfunction "TA1_2") (pintype "passive"))
    )
    (net (code "52") (name "Net-(U3A-TG1)") (class "Default")
      (node (ref "R13") (pin "3") (pinfunction "3_3") (pintype "passive"))
      (node (ref "U3") (pin "1") (pinfunction "TG1_1") (pintype "passive"))
    )
    (net (code "53") (name "Net-(U3B-T2)") (class "Default")
      (node (ref "R27") (pin "2") (pinfunction "2_2") (pintype "passive"))
      (node (ref "U3") (pin "6") (pinfunction "T2_6") (pintype "passive"))
    )
    (net (code "54") (name "Net-(U3B-TA2)") (class "Default")
      (node (ref "C10") (pin "1") (pinfunction "1_1") (pintype "passive"))
      (node (ref "R33") (pin "1") (pinfunction "1_1") (pintype "passive"))
      (node (ref "U3") (pin "5") (pinfunction "TA2_5") (pintype "passive"))
    )
    (net (code "55") (name "Net-(U3B-TG2)") (class "Default")
      (node (ref "C13") (pin "1") (pinfunction "1_1") (pintype "passive"))
      (node (ref "R36") (pin "2") (pinfunction "2_2") (pintype "passive"))
      (node (ref "U3") (pin "4") (pinfunction "TG2_4") (pintype "passive"))
    )
    (net (code "56") (name "Net-(U3C-H2)") (class "Default")
      (node (ref "R37") (pin "2") (pinfunction "2_2") (pintype "passive"))
      (node (ref "R7") (pin "1") (pinfunction "1_1") (pintype "passive"))
      (node (ref "U3") (pin "8") (pinfunction "H2_8") (pintype "passive"))
      (node (ref "U4") (pin "7") (pinfunction "H1_7") (pintype "passive"))
    )
    (net (code "57") (name "Net-(U4A-T1)") (class "Default")
      (node (ref "R54") (pin "2") (pinfunction "2_2") (pintype "passive"))
      (node (ref "U4") (pin "3") (pinfunction "T1_3") (pintype "passive"))
    )
    (net (code "58") (name "Net-(U4A-TA1)") (class "Default")
      (node (ref "C18") (pin "1") (pinfunction "1_1") (pintype "passive"))
      (node (ref "R53") (pin "1") (pinfunction "1_1") (pintype "passive"))
      (node (ref "U4") (pin "2") (pinfunction "TA1_2") (pintype "passive"))
    )
    (net (code "59") (name "Net-(U4A-TG1)") (class "Default")
      (node (ref "C21") (pin "1") (pinfunction "1_1") (pintype "passive"))
      (node (ref "R59") (pin "2") (pinfunction "2_2") (pintype "passive"))
      (node (ref "U4") (pin "1") (pinfunction "TG1_1") (pintype "passive"))
    )
    (net (code "60") (name "Net-(U4B-T2)") (class "Default")
      (node (ref "C17") (pin "+") (pinfunction "+_+") (pintype "passive"))
      (node (ref "R58") (pin "1") (pinfunction "1_1") (pintype "passive"))
      (node (ref "U4") (pin "6") (pinfunction "T2_6") (pintype "passive"))
    )
    (net (code "61") (name "Net-(U4B-TA2)") (class "Default")
      (node (ref "C21") (pin "2") (pinfunction "2_2") (pintype "passive"))
      (node (ref "R42") (pin "1") (pinfunction "1_1") (pintype "passive"))
      (node (ref "U4") (pin "5") (pinfunction "TA2_5") (pintype "passive"))
    )
    (net (code "62") (name "Net-(U4B-TG2)") (class "Default")
      (node (ref "R40") (pin "3") (pinfunction "3_3") (pintype "passive"))
      (node (ref "U4") (pin "4") (pinfunction "TG2_4") (pintype "passive"))
    )
    (net (code "63") (name "Net-(U4C-H2)") (class "Default")
      (node (ref "R37") (pin "1") (pinfunction "1_1") (pintype "passive"))
      (node (ref "U4") (pin "8") (pinfunction "H2_8") (pintype "passive"))
      (node (ref "U5") (pin "7") (pinfunction "H2_7") (pintype "passive"))
    )
    (net (code "64") (name "Net-(U5A-PA)") (class "Default")
      (node (ref "TR2") (pin "GRN@2") (pinfunction "GRN_GRN@2") (pintype "passive"))
      (node (ref "U5") (pin "3") (pinfunction "PA_3") (pintype "passive"))
    )
    (net (code "65") (name "Net-(U5A-PG)") (class "Default")
      (node (ref "R43") (pin "1") (pinfunction "1_1") (pintype "passive"))
      (node (ref "U5") (pin "5") (pinfunction "PG_5") (pintype "passive"))
    )
    (net (code "66") (name "Net-(U5A-PK)") (class "Default")
      (node (ref "R46") (pin "1") (pinfunction "1_1") (pintype "passive"))
      (node (ref "U5") (pin "8") (pinfunction "PK_8") (pintype "passive"))
    )
    (net (code "67") (name "Net-(U5A-PSG)") (class "Default")
      (node (ref "R47") (pin "1") (pinfunction "1_1") (pintype "passive"))
      (node (ref "U5") (pin "4") (pinfunction "PSG_4") (pintype "passive"))
    )
    (net (code "68") (name "Net-(U5A-SH)") (class "Default")
      (node (ref "C18") (pin "2") (pinfunction "2_2") (pintype "passive"))
      (node (ref "R43") (pin "2") (pinfunction "2_2") (pintype "passive"))
      (node (ref "R45") (pin "1") (pinfunction "1_1") (pintype "passive"))
      (node (ref "U5") (pin "1") (pinfunction "SH_1") (pintype "passive"))
    )
    (net (code "69") (name "Net-(U5B-H1)") (class "Default")
      (node (ref "U5") (pin "2") (pinfunction "H1_2") (pintype "passive"))
      (node (ref "U6") (pin "7") (pinfunction "H2_7") (pintype "passive"))
    )
    (net (code "70") (name "Net-(U6A-PA)") (class "Default")
      (node (ref "TR2") (pin "GRN@1") (pinfunction "GRN_GRN@1") (pintype "passive"))
      (node (ref "U6") (pin "3") (pinfunction "PA_3") (pintype "passive"))
    )
    (net (code "71") (name "Net-(U6A-PG)") (class "Default")
      (node (ref "R44") (pin "1") (pinfunction "1_1") (pintype "passive"))
      (node (ref "U6") (pin "5") (pinfunction "PG_5") (pintype "passive"))
    )
    (net (code "72") (name "Net-(U6A-PK)") (class "Default")
      (node (ref "R48") (pin "1") (pinfunction "1_1") (pintype "passive"))
      (node (ref "U6") (pin "8") (pinfunction "PK_8") (pintype "passive"))
    )
    (net (code "73") (name "Net-(U6A-PSG)") (class "Default")
      (node (ref "R50") (pin "1") (pinfunction "1_1") (pintype "passive"))
      (node (ref "U6") (pin "4") (pinfunction "PSG_4") (pintype "passive"))
    )
    (net (code "74") (name "Net-(U6A-SH)") (class "Default")
      (node (ref "C19") (pin "2") (pinfunction "2_2") (pintype "passive"))
      (node (ref "R44") (pin "2") (pinfunction "2_2") (pintype "passive"))
      (node (ref "R49") (pin "1") (pinfunction "1_1") (pintype "passive"))
      (node (ref "U6") (pin "1") (pinfunction "SH_1") (pintype "passive"))
    )
    (net (code "76") (name "unconnected-(R13-Pad2)") (class "Default")
      (node (ref "R13") (pin "2") (pinfunction "2_2") (pintype "passive"))
    )
    (net (code "77") (name "unconnected-(R40-Pad2)") (class "Default")
      (node (ref "R40") (pin "2") (pinfunction "2_2") (pintype "passive"))
    )
    (net (code "78") (name "unconnected-(S1A-O-Pad1)") (class "Default")
      (node (ref "S1") (pin "1") (pinfunction "O_1") (pintype "passive"))
    )
    (net (code "79") (name "unconnected-(S1B-O-Pad4)") (class "Default")
      (node (ref "S1") (pin "4") (pinfunction "O_4") (pintype "passive"))
    )
    (net (code "80") (name "unconnected-(S1B-P-Pad5)") (class "Default")
      (node (ref "S1") (pin "5") (pinfunction "P_5") (pintype "passive"))
    )
    (net (code "81") (name "unconnected-(U1B-H2-Pad7)") (class "Default")
      (node (ref "U1") (pin "7") (pinfunction "H2_7") (pintype "passive"))
    )
  )
)
